# Power_management.net
KiCad netlist of a schematic drawn in Altium Designer
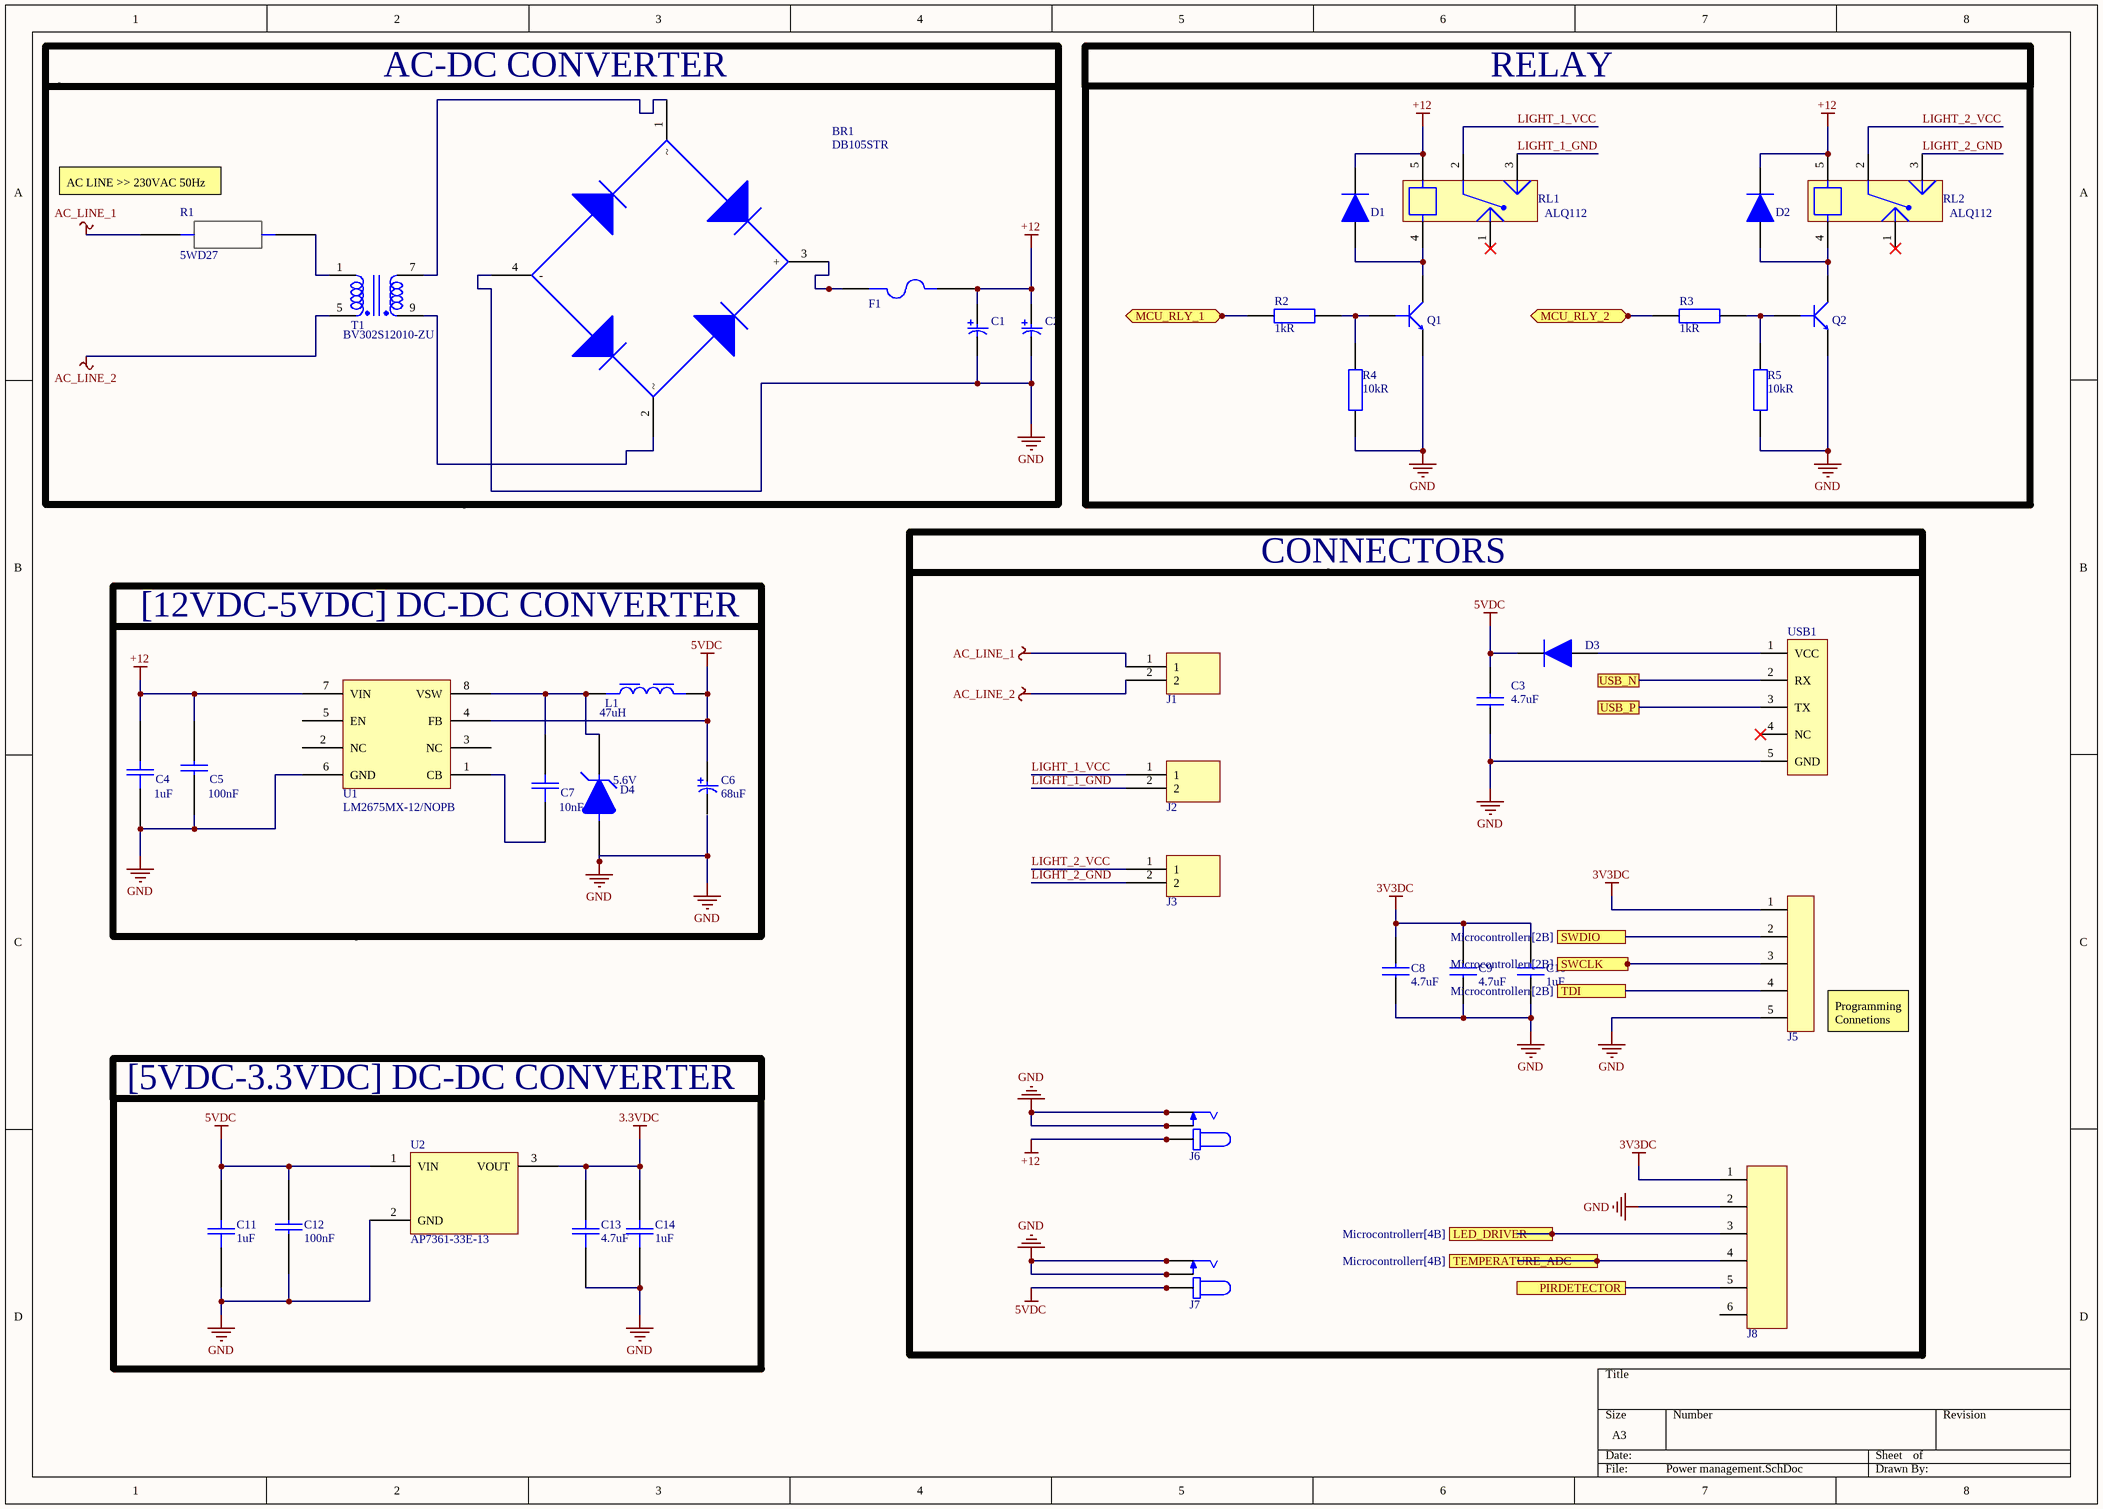
[diagram p0: Power management.SchDoc]

(export (version "E")
  (design (tool "Eeschema 10.0.6"))
  (components
    (comp (ref "BR1")
      (value "DB105STR")
      (footprint "DB105STR")
      (description "Bridge Rect 1PHASE 600V 1A Db-s")
      (fields (field (name "MANUFACTURER") "SMC") (field (name "DESIGNED BY") "ismet Akalın"))
      (libsource (lib "firstpcblib") (part "DB105STR"))
    )
    (comp (ref "C1")
      (value "ESH477M050AH4AA")
      (footprint "CAP_RADIAL_D10_P5")
      (description "CAP ALUM 470UF 20% 50V RADIAL TH")
      (fields (field (name "MANUFACTURER") "KEMET") (field (name "DESIGNED BY") "ismet Akalın"))
      (libsource (lib "firstpcblib") (part "CAP ALUM 470 uF %20"))
    )
    (comp (ref "C2")
      (value "ESH477M050AH4AA")
      (footprint "CAP_RADIAL_D10_P5")
      (description "CAP ALUM 470UF 20% 50V RADIAL TH")
      (fields (field (name "MANUFACTURER") "KEMET") (field (name "DESIGNED BY") "ismet Akalın"))
      (libsource (lib "firstpcblib") (part "CAP ALUM 470 uF %20"))
    )
    (comp (ref "C3")
      (value "CL21A475KAQNNNE")
      (footprint "CAP_0805")
      (description "CAP CER 4.7uF %10 0805")
      (fields
        (field (name "MANUFACTURER") "Samsung")
        (field (name "TOLERANCE") "10%")
        (field (name "CAPACITANCE") "4.7uF")
        (field (name "DESIGNED BY") "BERK")
      )
      (libsource (lib "UDEMY_Library") (part "CAP CER 4.7uF 0805"))
    )
    (comp (ref "C4")
      (value "1uF")
      (footprint "CAP_0805")
      (description "CAP CER 1uF %10 0805 -- CL21B105KBFNNNE")
      (fields
        (field (name "MANUFACTURER") "Samsung")
        (field (name "MANUFACTURER PART NUMBER") "CL21B105KBFNNNE")
        (field (name "DESIGNED BY") "ismet Akalın")
      )
      (libsource (lib "firstpcblib") (part "CAP CER 1uF %10 0805"))
    )
    (comp (ref "C5")
      (value "100nF")
      (footprint "CAP_0805")
      (description "CAP CER 100nF %10 0805 --CL21B104KBCNNNC")
      (fields
        (field (name "MANUFACTURER") "Samsung")
        (field (name "MANUFACTURER PART NUMBER") "CL21B104KBCNNNC")
        (field (name "DESIGNED BY") "ismet Akalın")
      )
      (libsource (lib "firstpcblib") (part "CAP CER 100nF %10 0805"))
    )
    (comp (ref "C6")
      (value "68uF")
      (footprint "EEV Series")
      (description "CAP ALUM 68uF %20 EEV Series")
      (fields
        (field (name "MANUFACTURER") "KEMET")
        (field (name "MANUFACTURER PART NUMBER") "EEV686M035A9HAA")
        (field (name "DESIGNED BY") "ismet Akalın")
      )
      (libsource (lib "firstpcblib") (part "CAP ALUM 68uF %20 EEV Series"))
    )
    (comp (ref "C7")
      (value "10nF")
      (footprint "CAP_0603")
      (description "CAP CER 10nF %10 0603 0603B103K160CT")
      (fields
        (field (name "MANUFACTURER") "Walsin Technologies")
        (field (name "MANUFACTURER PART NUMBER") "0603B103K160CT")
        (field (name "DESIGNED BY") "ismet Akalın")
      )
      (libsource (lib "firstpcblib") (part "CAP CER 10nF %10 0603"))
    )
    (comp (ref "C8")
      (value "CL21A475KAQNNNE")
      (footprint "CAP_0805")
      (description "CAP CER 4.7uF %10 0805")
      (fields
        (field (name "MANUFACTURER") "Samsung")
        (field (name "TOLERANCE") "10%")
        (field (name "CAPACITANCE") "4.7uF")
        (field (name "DESIGNED BY") "BERK")
      )
      (libsource (lib "UDEMY_Library") (part "CAP CER 4.7uF 0805"))
    )
    (comp (ref "C9")
      (value "CL21A475KAQNNNE")
      (footprint "CAP_0805")
      (description "CAP CER 4.7uF %10 0805")
      (fields
        (field (name "MANUFACTURER") "Samsung")
        (field (name "TOLERANCE") "10%")
        (field (name "CAPACITANCE") "4.7uF")
        (field (name "DESIGNED BY") "BERK")
      )
      (libsource (lib "UDEMY_Library") (part "CAP CER 4.7uF 0805"))
    )
    (comp (ref "C10")
      (value "CL21B105KBFNNNE")
      (footprint "CAP_0805")
      (description "CAP CER 1uF %10 0805")
      (fields
        (field (name "MANUFACTURER") "Samsung")
        (field (name "TOLERANCE") "10%")
        (field (name "CAPACITANCE") "1uF")
        (field (name "DESIGNED BY") "BERK")
      )
      (libsource (lib "UDEMY_Library") (part "CAP CER 1uF 0805"))
    )
    (comp (ref "C11")
      (value "1uF")
      (footprint "CAP_0805")
      (description "CAP CER 1uF %10 0805")
      (fields
        (field (name "MANUFACTURER") "Samsung")
        (field (name "MANUFACTURER PART NUMBER") "CL21B105KBFNNNE")
        (field (name "DESIGNED BY") "ismet Akalın")
      )
      (libsource (lib "firstpcblib") (part "CAP CER 1uF %10 0805"))
    )
    (comp (ref "C12")
      (value "100nF")
      (footprint "CAP_0603")
      (description "CAP CER 100nF %10 0603 SMD")
      (fields
        (field (name "MANUFACTURER") "KEMET")
        (field (name "MANUFACTURER PART NUMBER") "C0603C104K5RACTU")
        (field (name "DESIGNED BY") "ismet Akalın")
      )
      (libsource (lib "firstpcblib") (part "CAP CER 100nF 0603"))
    )
    (comp (ref "C13")
      (value "4.7uF")
      (footprint "CAP_0805")
      (description "CAP CER 4.7uF %10 0805")
      (fields
        (field (name "MANUFACTURER") "Samsung")
        (field (name "MANUFACTURER PART NUMBER") "CL21A475KAQNNNE")
        (field (name "DESIGNED BY") "ismet Akalın")
      )
      (libsource (lib "firstpcblib") (part "CAP CER 4.7uF %10 0805"))
    )
    (comp (ref "C14")
      (value "1uF")
      (footprint "CAP_0805")
      (description "CAP CER 1uF %10 0805")
      (fields
        (field (name "MANUFACTURER") "Samsung")
        (field (name "MANUFACTURER PART NUMBER") "CL21B105KBFNNNE")
        (field (name "DESIGNED BY") "ismet Akalın")
      )
      (libsource (lib "firstpcblib") (part "CAP CER 1uF %10 0805"))
    )
    (comp (ref "D1")
      (value "1N4148WS")
      (footprint "SOD323F")
      (description "Diode, Single, 75 V, 150 mA, 1 V, 4 ns")
      (fields
        (field (name "MANUFACTURER") "ON Semiconductor / Fairchild")
        (field (name "DESIGNED BY") "BERK")
      )
      (libsource (lib "UDEMY_Library") (part "1N4148WS"))
    )
    (comp (ref "D2")
      (value "1N4148WS")
      (footprint "SOD323F")
      (description "Diode, Single, 75 V, 150 mA, 1 V, 4 ns")
      (fields
        (field (name "MANUFACTURER") "ON Semiconductor / Fairchild")
        (field (name "DESIGNED BY") "BERK")
      )
      (libsource (lib "UDEMY_Library") (part "1N4148WS"))
    )
    (comp (ref "D3")
      (value "1N4148WS")
      (footprint "SOD323F")
      (description "Diode, Single, 75 V, 150 mA, 1 V, 4 ns")
      (fields
        (field (name "MANUFACTURER") "ON Semiconductor / Fairchild")
        (field (name "DESIGNED BY") "BERK")
      )
      (libsource (lib "UDEMY_Library") (part "1N4148WS"))
    )
    (comp (ref "D4")
      (value "1SMB5919BT3G")
      (footprint "SMB")
      (description "Zener Diode, 5.6V V(Z), 5%, 0.55W, Silicon, Unidirectional, DO-214AA")
      (fields
        (field (name "MANUFACTURER") "ON Semiconductor")
        (field (name "REFERENCE VOLTAGE-NOM") "5.6V")
        (field (name "DESIGNED BY") "ismet Akalın")
      )
      (libsource (lib "firstpcblib") (part "1SMB5919BT3G"))
    )
    (comp (ref "F1")
      (value "3413.0216.22")
      (footprint "3413.0216.22")
      (description "Electric Fuse, Very Fast Blow, 1A, 32VAC, 63VDC, 63A (IR), Surface Mount, 1206")
      (fields (field (name "MANUFACTURER") "Schurter") (field (name "DESIGNED BY") "ismet Akalın"))
      (libsource (lib "firstpcblib") (part "3413.0216.22"))
    )
    (comp (ref "J1")
      (value "TBP01R1-508-02BE")
      (footprint "TBP01R1-508")
      (description "Strip Terminal Block")
      (fields (field (name "MANUFACTURER") "CUI Devices") (field (name "DESIGNED BY") "ismet Akalın"))
      (libsource (lib "firstpcblib") (part "TBP01R1-508-02BE"))
    )
    (comp (ref "J2")
      (value "TBP01R1-508-02BE")
      (footprint "TBP01R1-508")
      (description "Strip Terminal Block")
      (fields (field (name "MANUFACTURER") "CUI Devices") (field (name "DESIGNED BY") "ismet Akalın"))
      (libsource (lib "firstpcblib") (part "TBP01R1-508-02BE"))
    )
    (comp (ref "J3")
      (value "TBP01R1-508-02BE")
      (footprint "TBP01R1-508")
      (description "Strip Terminal Block")
      (fields (field (name "MANUFACTURER") "CUI Devices") (field (name "DESIGNED BY") "ismet Akalın"))
      (libsource (lib "firstpcblib") (part "TBP01R1-508-02BE"))
    )
    (comp (ref "J5")
      (value "SMH-105-02-L-S")
      (footprint "PINHEADER1X5_RA")
      (description ".100 C.L. HORIZONTAL SMT SOCKET")
      (fields (field (name "MANUFACTURER") "Samtec") (field (name "DESIGNED BY") "BERK"))
      (libsource (lib "UDEMY_Library") (part "SMH-105-02-L-S"))
    )
    (comp (ref "J6")
      (value "PJ-037AH-SMT-TR")
      (footprint "JACK")
      (fields (field (name "MANUFACTURER") "CUI") (field (name "DESIGNED BY") "ismet Akalın"))
      (libsource (lib "firstpcblib") (part "PJ-037AH-SMT-TR"))
    )
    (comp (ref "J7")
      (value "PJ-037AH-SMT-TR")
      (footprint "JACK")
      (fields (field (name "MANUFACTURER") "CUI") (field (name "DESIGNED BY") "ismet Akalın"))
      (libsource (lib "firstpcblib") (part "PJ-037AH-SMT-TR"))
    )
    (comp (ref "J8")
      (value "64800611622")
      (footprint "64800611622")
      (description "1.50mm 6PIN Connector")
      (fields (field (name "MANUFACTURER") "Wurth Electronics"))
      (libsource (lib "UDEMY_Library") (part "64800611622_conn_6pin"))
    )
    (comp (ref "L1")
      (value "47uH")
      (footprint "IND_1212")
      (description "FIXED IND 47UH 390MA 2.3 OHM SMD 78438335470")
      (fields
        (field (name "MANUFACTURER") "Wurth Electronics")
        (field (name "MANUFACTURER PART NUMBER") "78438335470")
        (field (name "DESIGNED BY") "ismet Akalın")
      )
      (libsource (lib "firstpcblib") (part "78438335470"))
    )
    (comp (ref "Q1")
      (value "MMBT3904-7-F")
      (footprint "SOT-23F")
      (description "Transistor General Purpose BJT NPN 40 Volt 0.2A Automotive 3-Pin SOT-23")
      (fields (field (name "MANUFACTURER") "Diodes Zetex") (field (name "DESIGNED BY") "BERK"))
      (libsource (lib "UDEMY_Library") (part "MMBT3904-7-F"))
    )
    (comp (ref "Q2")
      (value "MMBT3904-7-F")
      (footprint "SOT-23F")
      (description "Transistor General Purpose BJT NPN 40 Volt 0.2A Automotive 3-Pin SOT-23")
      (fields (field (name "MANUFACTURER") "Diodes Zetex") (field (name "DESIGNED BY") "BERK"))
      (libsource (lib "UDEMY_Library") (part "MMBT3904-7-F"))
    )
    (comp (ref "R1")
      (value "5WD27")
      (footprint "RES_AXIAL_W")
      (description "Fixed Resistor, Wire Wound, 5W, 0.27ohm, 200V, 5% +/-Tol, 300ppm/Cel, 8738")
      (fields
        (field (name "MANUFACTURER") "NTE Electronics")
        (field (name "POWER") "5W")
        (field (name "DESIGNED BY") "ismet Akalın")
      )
      (libsource (lib "firstpcblib") (part "5WD27"))
    )
    (comp (ref "R2")
      (value "RC0603FR-0710KL")
      (footprint "RES_0603")
      (description "RES 1K %1 OHM 0603 SMD")
      (fields
        (field (name "MANUFACTURER") "Yageo")
        (field (name "MANUFACTURER PART NUMBER") "RC0603JR-071KL")
        (field (name "RESISTANCE") "1kR")
        (field (name "DESIGNED BY") "BERK")
      )
      (libsource (lib "UDEMY_Library") (part "RES 1K OHM 0603"))
    )
    (comp (ref "R3")
      (value "RC0603FR-0710KL")
      (footprint "RES_0603")
      (description "RES 1K %1 OHM 0603 SMD")
      (fields
        (field (name "MANUFACTURER") "Yageo")
        (field (name "MANUFACTURER PART NUMBER") "RC0603JR-071KL")
        (field (name "RESISTANCE") "1kR")
        (field (name "DESIGNED BY") "BERK")
      )
      (libsource (lib "UDEMY_Library") (part "RES 1K OHM 0603"))
    )
    (comp (ref "R4")
      (value "RC0603FR-0710KL")
      (footprint "RES_0603")
      (description "RES 10K %1 OHM 0603 SMD")
      (fields
        (field (name "MANUFACTURER") "Yageo")
        (field (name "TOLERANCE") "1%")
        (field (name "RESISTANCE") "10kR")
        (field (name "DESIGNED BY") "BERK")
      )
      (libsource (lib "UDEMY_Library") (part "RES 10K OHM 0603"))
    )
    (comp (ref "R5")
      (value "RC0603FR-0710KL")
      (footprint "RES_0603")
      (description "RES 10K %1 OHM 0603 SMD")
      (fields
        (field (name "MANUFACTURER") "Yageo")
        (field (name "TOLERANCE") "1%")
        (field (name "RESISTANCE") "10kR")
        (field (name "DESIGNED BY") "BERK")
      )
      (libsource (lib "UDEMY_Library") (part "RES 10K OHM 0603"))
    )
    (comp (ref "RL1")
      (value "ALQ112")
      (footprint "ALQ112")
      (fields (field (name "MANUFACTURER") "Panasonic") (field (name "DESIGNED BY") "ismet Akalın"))
      (libsource (lib "firstpcblib") (part "ALQ112"))
    )
    (comp (ref "RL2")
      (value "ALQ112")
      (footprint "ALQ112")
      (fields (field (name "MANUFACTURER") "Panasonic") (field (name "DESIGNED BY") "ismet Akalın"))
      (libsource (lib "firstpcblib") (part "ALQ112"))
    )
    (comp (ref "T1")
      (value "BV302S12010-ZU")
      (footprint "BV3025")
      (description "230-12 Transformer 1VA")
      (fields (field (name "MANUFACTURER") "Zettler Magnetics") (field (name "DESIGNED BY") "ismet Akalın"))
      (libsource (lib "firstpcblib") (part "BV302S12010-ZU"))
    )
    (comp (ref "U1")
      (value "LM2675MX-12/NOPB")
      (footprint "SOIC8")
      (description "Switching Regulator, Voltage-mode, 2.2A, 275kHz Switching Freq-Max, DMOS, PDSO8")
      (fields
        (field (name "MANUFACTURER") "TI National Semiconductor")
        (field (name "DESIGNED BY") "ismet Akalın")
      )
      (libsource (lib "firstpcblib") (part "LM2675MX-12/NOPB"))
    )
    (comp (ref "U2")
      (value "AP7361-33E-13")
      (footprint "SOT223")
      (description "Fixed Positive LDO Regulator, 3.3V, 0.7V Dropout, CMOS, PSSO3")
      (fields (field (name "MANUFACTURER") "Diodes") (field (name "DESIGNED BY") "ismet Akalın"))
      (libsource (lib "firstpcblib") (part "AP7361-33E-13"))
    )
    (comp (ref "USB1")
      (value "10118192-0001LF")
      (footprint "MICRO_B_USB")
      (description "CONN RCPT USB2.0 MICRO B SMD R/A")
      (fields (field (name "MANUFACTURER") "Amphenol FCI") (field (name "DESIGNED BY") "BERK"))
      (libsource (lib "UDEMY_Library") (part "Micro B USB Connector"))
    )
  )
  (nets
    (net (code "1") (name "+12") (class "Default")
      (node (ref "C1") (pin "1") (pinfunction "1_1") (pintype "passive"))
      (node (ref "C2") (pin "1") (pinfunction "1_1") (pintype "passive"))
      (node (ref "C4") (pin "2") (pinfunction "2_2") (pintype "passive"))
      (node (ref "C5") (pin "2") (pinfunction "2_2") (pintype "passive"))
      (node (ref "D1") (pin "1") (pinfunction "1_1") (pintype "power_in"))
      (node (ref "D2") (pin "1") (pinfunction "1_1") (pintype "power_in"))
      (node (ref "F1") (pin "2") (pinfunction "2_2") (pintype "passive"))
      (node (ref "J6") (pin "1A") (pinfunction "1_1A") (pintype "passive"))
      (node (ref "J6") (pin "1B") (pinfunction "1_1B") (pintype "passive"))
      (node (ref "RL1") (pin "5") (pinfunction "5_5") (pintype "passive"))
      (node (ref "RL2") (pin "5") (pinfunction "5_5") (pintype "passive"))
      (node (ref "U1") (pin "7") (pinfunction "VIN_7") (pintype "passive"))
    )
    (net (code "2") (name "/LED_DRIVER") (class "Default") (node (ref "J8") (pin "3") (pintype "power_in")))
    (net (code "3") (name "/LIGHT_1_GND") (class "Default")
      (node (ref "J2") (pin "2") (pinfunction "2_2") (pintype "passive"))
      (node (ref "RL1") (pin "3") (pinfunction "3_3") (pintype "passive"))
    )
    (net (code "4") (name "/LIGHT_1_VCC") (class "Default")
      (node (ref "J2") (pin "1") (pinfunction "1_1") (pintype "passive"))
      (node (ref "RL1") (pin "2") (pinfunction "2_2") (pintype "passive"))
    )
    (net (code "5") (name "/LIGHT_2_GND") (class "Default")
      (node (ref "J3") (pin "2") (pinfunction "2_2") (pintype "passive"))
      (node (ref "RL2") (pin "3") (pinfunction "3_3") (pintype "passive"))
    )
    (net (code "6") (name "/LIGHT_2_VCC") (class "Default")
      (node (ref "J3") (pin "1") (pinfunction "1_1") (pintype "passive"))
      (node (ref "RL2") (pin "2") (pinfunction "2_2") (pintype "passive"))
    )
    (net (code "7") (name "/MCU_RLY_1") (class "Default")
      (node (ref "R2") (pin "1") (pinfunction "1_1") (pintype "passive"))
    )
    (net (code "8") (name "/MCU_RLY_2") (class "Default")
      (node (ref "R3") (pin "1") (pinfunction "1_1") (pintype "passive"))
    )
    (net (code "9") (name "/PIRDETECTOR") (class "Default") (node (ref "J8") (pin "5") (pintype "power_in")))
    (net (code "10") (name "/SWCLK") (class "Default")
      (node (ref "J5") (pin "3") (pinfunction "3_3") (pintype "power_in"))
    )
    (net (code "11") (name "/SWDIO") (class "Default")
      (node (ref "J5") (pin "2") (pinfunction "2_2") (pintype "power_in"))
    )
    (net (code "12") (name "/TDI") (class "Default")
      (node (ref "J5") (pin "4") (pinfunction "4_4") (pintype "power_in"))
    )
    (net (code "13") (name "/TEMPERATURE_ADC") (class "Default")
      (node (ref "J8") (pin "4") (pintype "power_in"))
    )
    (net (code "14") (name "/USB_N") (class "Default")
      (node (ref "USB1") (pin "2") (pinfunction "RX_2") (pintype "power_in"))
    )
    (net (code "15") (name "/USB_P") (class "Default")
      (node (ref "USB1") (pin "3") (pinfunction "TX_3") (pintype "power_in"))
    )
    (net (code "16") (name "3.3VDC") (class "Default")
      (node (ref "C13") (pin "2") (pinfunction "2_2") (pintype "passive"))
      (node (ref "C14") (pin "2") (pinfunction "2_2") (pintype "passive"))
      (node (ref "U2") (pin "3") (pinfunction "VOUT_3") (pintype "passive"))
    )
    (net (code "17") (name "3V3DC") (class "Default")
      (node (ref "C10") (pin "2") (pinfunction "2_2") (pintype "passive"))
      (node (ref "C8") (pin "2") (pinfunction "2_2") (pintype "passive"))
      (node (ref "C9") (pin "2") (pinfunction "2_2") (pintype "passive"))
      (node (ref "J5") (pin "1") (pinfunction "1_1") (pintype "power_in"))
      (node (ref "J8") (pin "1") (pintype "power_in"))
    )
    (net (code "18") (name "5VDC") (class "Default")
      (node (ref "C11") (pin "2") (pinfunction "2_2") (pintype "passive"))
      (node (ref "C12") (pin "2") (pinfunction "2_2") (pintype "passive"))
      (node (ref "C3") (pin "2") (pinfunction "2_2") (pintype "passive"))
      (node (ref "C6") (pin "1") (pinfunction "1_1") (pintype "passive"))
      (node (ref "D3") (pin "1") (pinfunction "1_1") (pintype "power_in"))
      (node (ref "J7") (pin "1A") (pinfunction "1_1A") (pintype "passive"))
      (node (ref "J7") (pin "1B") (pinfunction "1_1B") (pintype "passive"))
      (node (ref "L1") (pin "2") (pinfunction "2_2") (pintype "passive"))
      (node (ref "U1") (pin "4") (pinfunction "FB_4") (pintype "passive"))
      (node (ref "U2") (pin "1") (pinfunction "VIN_1") (pintype "passive"))
    )
    (net (code "19") (name "AC_LINE_1") (class "Default")
      (node (ref "J1") (pin "1") (pinfunction "1_1") (pintype "passive"))
      (node (ref "R1") (pin "1") (pinfunction "1_1") (pintype "passive"))
    )
    (net (code "20") (name "AC_LINE_2") (class "Default")
      (node (ref "J1") (pin "2") (pinfunction "2_2") (pintype "passive"))
      (node (ref "T1") (pin "5") (pinfunction "5_5") (pintype "passive"))
    )
    (net (code "21") (name "GND") (class "Default")
      (node (ref "BR1") (pin "4") (pinfunction "-_4") (pintype "passive"))
      (node (ref "C1") (pin "2") (pinfunction "2_2") (pintype "passive"))
      (node (ref "C10") (pin "1") (pinfunction "1_1") (pintype "passive"))
      (node (ref "C11") (pin "1") (pinfunction "1_1") (pintype "passive"))
      (node (ref "C12") (pin "1") (pinfunction "1_1") (pintype "passive"))
      (node (ref "C13") (pin "1") (pinfunction "1_1") (pintype "passive"))
      (node (ref "C14") (pin "1") (pinfunction "1_1") (pintype "passive"))
      (node (ref "C2") (pin "2") (pinfunction "2_2") (pintype "passive"))
      (node (ref "C3") (pin "1") (pinfunction "1_1") (pintype "passive"))
      (node (ref "C4") (pin "1") (pinfunction "1_1") (pintype "passive"))
      (node (ref "C5") (pin "1") (pinfunction "1_1") (pintype "passive"))
      (node (ref "C8") (pin "1") (pinfunction "1_1") (pintype "passive"))
      (node (ref "C9") (pin "1") (pinfunction "1_1") (pintype "passive"))
      (node (ref "D4") (pin "C") (pinfunction "C_C") (pintype "passive"))
      (node (ref "J5") (pin "5") (pinfunction "5_5") (pintype "power_in"))
      (node (ref "J6") (pin "2A") (pinfunction "2_2A") (pintype "passive"))
      (node (ref "J6") (pin "2B") (pinfunction "2_2B") (pintype "passive"))
      (node (ref "J6") (pin "3A") (pinfunction "3_3A") (pintype "passive"))
      (node (ref "J6") (pin "3B") (pinfunction "3_3B") (pintype "passive"))
      (node (ref "J7") (pin "2A") (pinfunction "2_2A") (pintype "passive"))
      (node (ref "J7") (pin "2B") (pinfunction "2_2B") (pintype "passive"))
      (node (ref "J7") (pin "3A") (pinfunction "3_3A") (pintype "passive"))
      (node (ref "J7") (pin "3B") (pinfunction "3_3B") (pintype "passive"))
      (node (ref "J8") (pin "2") (pintype "power_in"))
      (node (ref "Q1") (pin "2") (pinfunction "E_2") (pintype "power_in"))
      (node (ref "Q2") (pin "2") (pinfunction "E_2") (pintype "power_in"))
      (node (ref "R4") (pin "1") (pinfunction "1_1") (pintype "passive"))
      (node (ref "R5") (pin "1") (pinfunction "1_1") (pintype "passive"))
      (node (ref "U1") (pin "6") (pinfunction "GND_6") (pintype "passive"))
      (node (ref "U2") (pin "2") (pinfunction "GND_2") (pintype "passive"))
      (node (ref "USB1") (pin "5") (pinfunction "GND_5") (pintype "power_in"))
    )
    (net (code "22") (name "Net-(BR1-+)") (class "Default")
      (node (ref "BR1") (pin "3") (pinfunction "+_3") (pintype "passive"))
      (node (ref "F1") (pin "1") (pinfunction "1_1") (pintype "passive"))
    )
    (net (code "23") (name "Net-(BR1-~-Pad1)") (class "Default")
      (node (ref "BR1") (pin "1") (pinfunction "~_1") (pintype "passive"))
      (node (ref "T1") (pin "7") (pinfunction "7_7") (pintype "passive"))
    )
    (net (code "24") (name "Net-(BR1-~-Pad2)") (class "Default")
      (node (ref "BR1") (pin "2") (pinfunction "~_2") (pintype "passive"))
      (node (ref "T1") (pin "9") (pinfunction "9_9") (pintype "passive"))
    )
    (net (code "25") (name "Net-(Q1-B)") (class "Default")
      (node (ref "Q1") (pin "1") (pinfunction "B_1") (pintype "power_in"))
      (node (ref "R2") (pin "2") (pinfunction "2_2") (pintype "passive"))
      (node (ref "R4") (pin "2") (pinfunction "2_2") (pintype "passive"))
    )
    (net (code "26") (name "Net-(Q1-C)") (class "Default")
      (node (ref "D1") (pin "2") (pinfunction "2_2") (pintype "power_in"))
      (node (ref "Q1") (pin "3") (pinfunction "C_3") (pintype "power_in"))
      (node (ref "RL1") (pin "4") (pinfunction "_4_4") (pintype "passive"))
    )
    (net (code "27") (name "Net-(Q2-B)") (class "Default")
      (node (ref "Q2") (pin "1") (pinfunction "B_1") (pintype "power_in"))
      (node (ref "R3") (pin "2") (pinfunction "2_2") (pintype "passive"))
      (node (ref "R5") (pin "2") (pinfunction "2_2") (pintype "passive"))
    )
    (net (code "28") (name "Net-(Q2-C)") (class "Default")
      (node (ref "D2") (pin "2") (pinfunction "2_2") (pintype "power_in"))
      (node (ref "Q2") (pin "3") (pinfunction "C_3") (pintype "power_in"))
      (node (ref "RL2") (pin "4") (pinfunction "_4_4") (pintype "passive"))
    )
    (net (code "29") (name "Net-(R1-Pad2)") (class "Default")
      (node (ref "R1") (pin "2") (pinfunction "2_2") (pintype "passive"))
      (node (ref "T1") (pin "1") (pinfunction "1_1") (pintype "passive"))
    )
    (net (code "30") (name "Net-(U1-CB)") (class "Default")
      (node (ref "C7") (pin "1") (pinfunction "1_1") (pintype "passive"))
      (node (ref "U1") (pin "1") (pinfunction "CB_1") (pintype "passive"))
    )
    (net (code "31") (name "Net-(U1-VSW)") (class "Default")
      (node (ref "C7") (pin "2") (pinfunction "2_2") (pintype "passive"))
      (node (ref "D4") (pin "A") (pinfunction "A_A") (pintype "passive"))
      (node (ref "L1") (pin "1") (pinfunction "1_1") (pintype "passive"))
      (node (ref "U1") (pin "8") (pinfunction "VSW_8") (pintype "passive"))
    )
    (net (code "32") (name "Net-(USB1-VCC)") (class "Default")
      (node (ref "D3") (pin "2") (pinfunction "2_2") (pintype "power_in"))
      (node (ref "USB1") (pin "1") (pinfunction "VCC_1") (pintype "power_in"))
    )
    (net (code "33") (name "unconnected-(C6-Pad2)") (class "Default")
      (node (ref "C6") (pin "2") (pinfunction "2_2") (pintype "passive"))
    )
    (net (code "34") (name "unconnected-(J8-Pad6)") (class "Default")
      (node (ref "J8") (pin "6") (pintype "power_in"))
    )
    (net (code "35") (name "unconnected-(RL1-Pad1)") (class "Default")
      (node (ref "RL1") (pin "1") (pinfunction "1_1") (pintype "passive+no_connect"))
    )
    (net (code "36") (name "unconnected-(RL2-Pad1)") (class "Default")
      (node (ref "RL2") (pin "1") (pinfunction "1_1") (pintype "passive+no_connect"))
    )
    (net (code "37") (name "unconnected-(U1-EN-Pad5)") (class "Default")
      (node (ref "U1") (pin "5") (pinfunction "EN_5") (pintype "passive"))
    )
    (net (code "38") (name "unconnected-(U1-NC-Pad2)") (class "Default")
      (node (ref "U1") (pin "2") (pinfunction "NC_2") (pintype "passive"))
    )
    (net (code "39") (name "unconnected-(U1-NC-Pad3)") (class "Default")
      (node (ref "U1") (pin "3") (pinfunction "NC_3") (pintype "passive"))
    )
    (net (code "40") (name "unconnected-(USB1-NC-Pad4)") (class "Default")
      (node (ref "USB1") (pin "4") (pinfunction "NC_4") (pintype "power_in+no_connect"))
    )
  )
)
